# HB-UNI-Sen-TEMP-DS18B20_V1_0.net
KiCad netlist of a schematic drawn in EAGLE
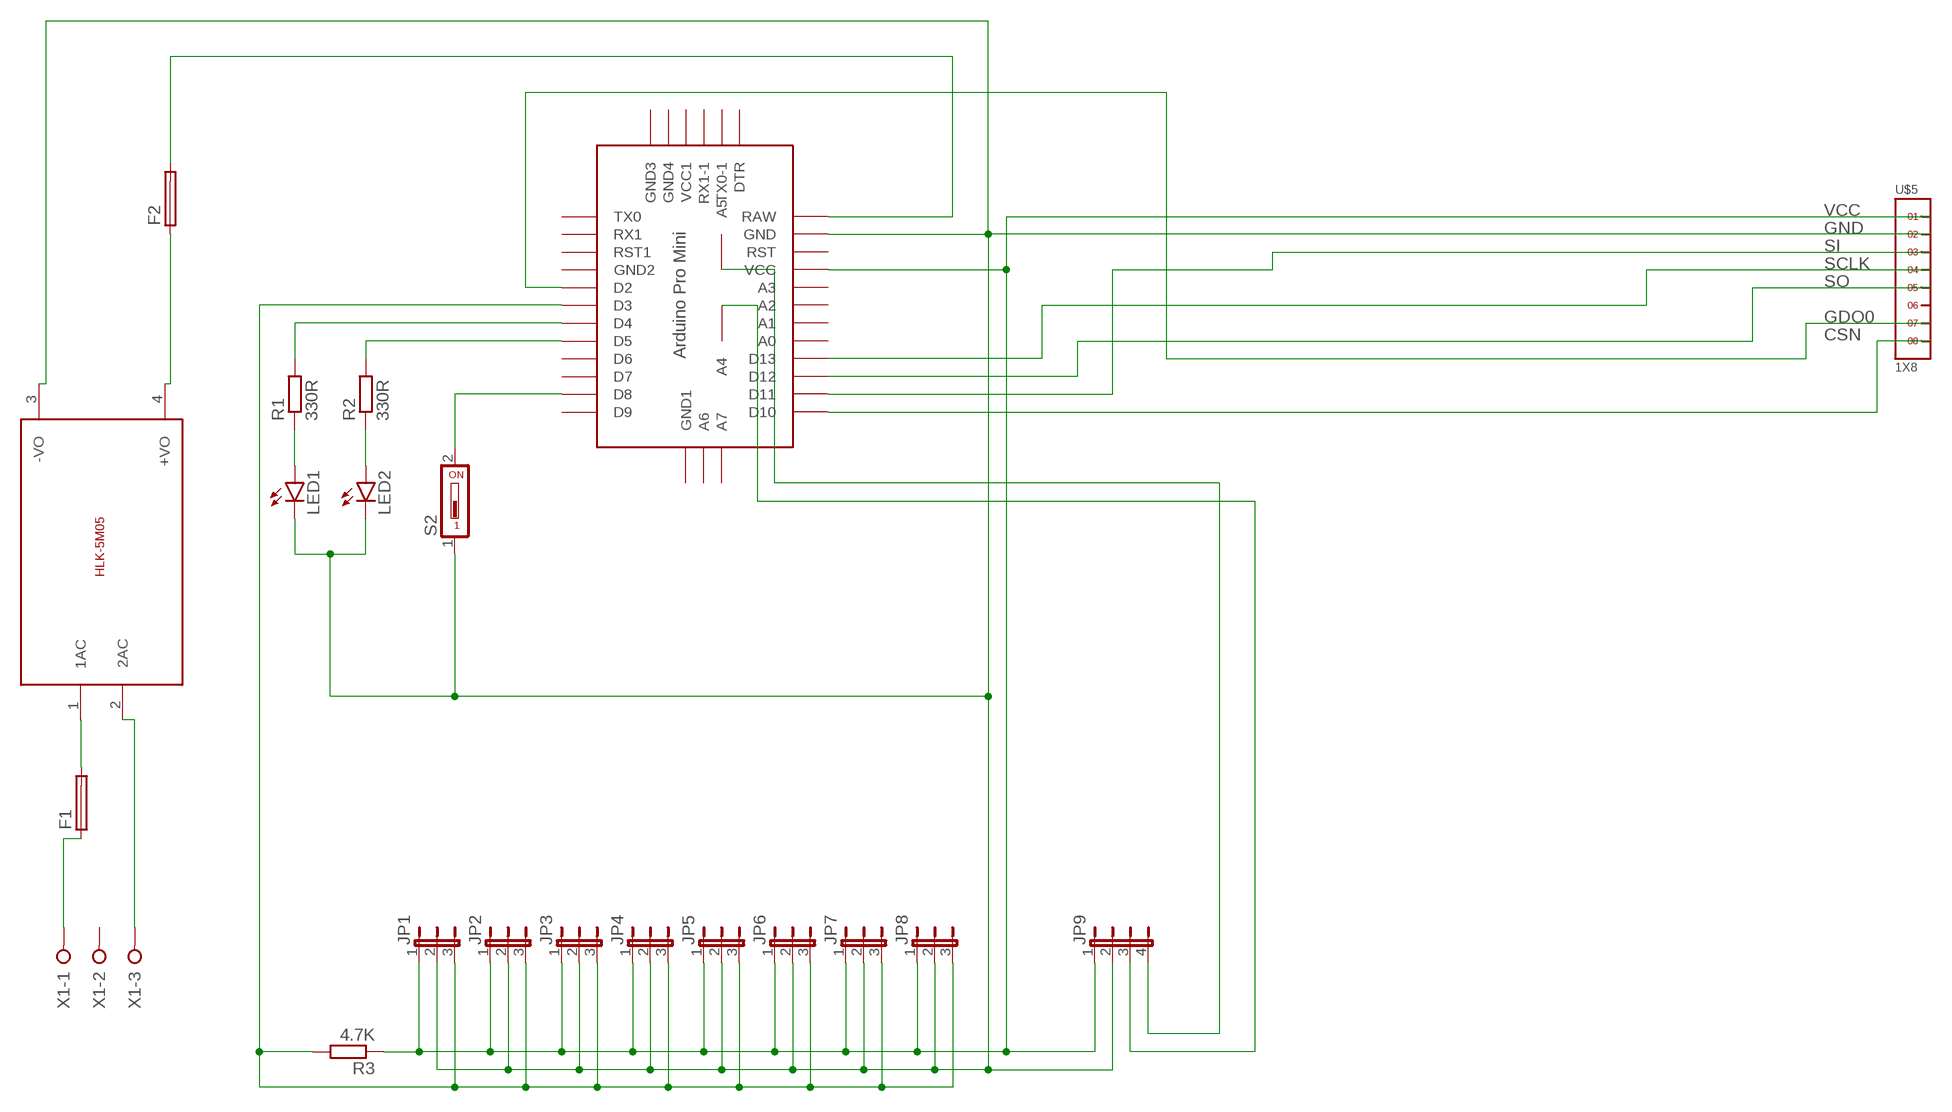
[diagram p0: schematic, sheet 1]

(export (version "E")
  (design (tool "Eeschema 10.0.6"))
  (components
    (comp (ref "F1")
      (value "GSH15")
      (footprint "eagle-import:GSH15")
      (fields (field (name "MPN") "64900001039"))
      (libsource (lib "eagle-import") (part "GSH15"))
    )
    (comp (ref "F2")
      (value "GSH15")
      (footprint "eagle-import:GSH15")
      (fields (field (name "MPN") "64900001039"))
      (libsource (lib "eagle-import") (part "GSH15"))
    )
    (comp (ref "JP1")
      (value "JP2W")
      (footprint "eagle-import:JP2W")
      (libsource (lib "eagle-import") (part "JP2W"))
    )
    (comp (ref "JP2")
      (value "JP2W")
      (footprint "eagle-import:JP2W")
      (libsource (lib "eagle-import") (part "JP2W"))
    )
    (comp (ref "JP3")
      (value "JP2W")
      (footprint "eagle-import:JP2W")
      (libsource (lib "eagle-import") (part "JP2W"))
    )
    (comp (ref "JP4")
      (value "JP2W")
      (footprint "eagle-import:JP2W")
      (libsource (lib "eagle-import") (part "JP2W"))
    )
    (comp (ref "JP5")
      (value "JP2W")
      (footprint "eagle-import:JP2W")
      (libsource (lib "eagle-import") (part "JP2W"))
    )
    (comp (ref "JP6")
      (value "JP2W")
      (footprint "eagle-import:JP2W")
      (libsource (lib "eagle-import") (part "JP2W"))
    )
    (comp (ref "JP7")
      (value "JP2W")
      (footprint "eagle-import:JP2W")
      (libsource (lib "eagle-import") (part "JP2W"))
    )
    (comp (ref "JP8")
      (value "JP2W")
      (footprint "eagle-import:JP2W")
      (libsource (lib "eagle-import") (part "JP2W"))
    )
    (comp (ref "JP9")
      (value "JP4E")
      (footprint "eagle-import:JP4")
      (libsource (lib "eagle-import") (part "JP4E"))
    )
    (comp (ref "LED1")
      (value "LED5MM")
      (footprint "eagle-import:LED5MM")
      (libsource (lib "eagle-import") (part "LED5MM"))
    )
    (comp (ref "LED2")
      (value "LED5MM")
      (footprint "eagle-import:LED5MM")
      (libsource (lib "eagle-import") (part "LED5MM"))
    )
    (comp (ref "R1")
      (value "330R")
      (footprint "eagle-import:0207_10")
      (libsource (lib "eagle-import") (part "R-EU_0207/10"))
    )
    (comp (ref "R2")
      (value "330R")
      (footprint "eagle-import:0207_10")
      (libsource (lib "eagle-import") (part "R-EU_0207/10"))
    )
    (comp (ref "R3")
      (value "4.7K")
      (footprint "eagle-import:0207_10")
      (libsource (lib "eagle-import") (part "R-EU_0207/10"))
    )
    (comp (ref "S2")
      (value "DS01")
      (footprint "eagle-import:DS-01")
      (libsource (lib "eagle-import") (part "DS01"))
    )
    (comp (ref "U$1")
      (value "ABK-PRO-MINI")
      (footprint "eagle-import:ABK-PRO-MINI")
      (libsource (lib "eagle-import") (part "ABK-PRO-MINI"))
    )
    (comp (ref "U$3")
      (value "5VDC/5W")
      (footprint "eagle-import:HLK-5M05")
      (libsource (lib "eagle-import") (part "HLK-5M05"))
    )
    (comp (ref "U$5")
      (value "1X8")
      (footprint "eagle-import:1X8")
      (libsource (lib "eagle-import") (part "1X8"))
    )
    (comp (ref "X1")
      (value "W237-3E")
      (footprint "eagle-import:W237-3E")
      (libsource (lib "eagle-import") (part "W237-3E"))
    )
  )
  (nets
    (net (code "1") (name "/CSN") (class "Default")
      (node (ref "U$1") (pin "D10") (pinfunction "D10_D10") (pintype "bidirectional"))
      (node (ref "U$5") (pin "8") (pinfunction "8_8") (pintype "bidirectional"))
    )
    (net (code "2") (name "/GDO0") (class "Default")
      (node (ref "U$1") (pin "D2") (pinfunction "D2_D2") (pintype "bidirectional"))
      (node (ref "U$5") (pin "7") (pinfunction "7_7") (pintype "bidirectional"))
    )
    (net (code "3") (name "/GND") (class "Default")
      (node (ref "JP1") (pin "2") (pinfunction "2_2") (pintype "passive"))
      (node (ref "JP2") (pin "2") (pinfunction "2_2") (pintype "passive"))
      (node (ref "JP3") (pin "2") (pinfunction "2_2") (pintype "passive"))
      (node (ref "JP4") (pin "2") (pinfunction "2_2") (pintype "passive"))
      (node (ref "JP5") (pin "2") (pinfunction "2_2") (pintype "passive"))
      (node (ref "JP6") (pin "2") (pinfunction "2_2") (pintype "passive"))
      (node (ref "JP7") (pin "2") (pinfunction "2_2") (pintype "passive"))
      (node (ref "JP8") (pin "2") (pinfunction "2_2") (pintype "passive"))
      (node (ref "JP9") (pin "2") (pinfunction "2_2") (pintype "passive"))
      (node (ref "LED1") (pin "K") (pinfunction "C_K") (pintype "passive"))
      (node (ref "LED2") (pin "K") (pinfunction "C_K") (pintype "passive"))
      (node (ref "S2") (pin "1") (pinfunction "1_1") (pintype "passive"))
      (node (ref "U$1") (pin "GND") (pinfunction "GND_GND") (pintype "bidirectional"))
      (node (ref "U$3") (pin "3") (pinfunction "-VO_3") (pintype "bidirectional"))
      (node (ref "U$5") (pin "2") (pinfunction "2_2") (pintype "bidirectional"))
    )
    (net (code "4") (name "/SCLK") (class "Default")
      (node (ref "U$1") (pin "D13") (pinfunction "D13_D13") (pintype "bidirectional"))
      (node (ref "U$5") (pin "4") (pinfunction "4_4") (pintype "bidirectional"))
    )
    (net (code "5") (name "/SI") (class "Default")
      (node (ref "U$1") (pin "D11") (pinfunction "D11_D11") (pintype "bidirectional"))
      (node (ref "U$5") (pin "3") (pinfunction "3_3") (pintype "bidirectional"))
    )
    (net (code "6") (name "/SO") (class "Default")
      (node (ref "U$1") (pin "D12") (pinfunction "D12_D12") (pintype "bidirectional"))
      (node (ref "U$5") (pin "5") (pinfunction "5_5") (pintype "bidirectional"))
    )
    (net (code "7") (name "/VCC") (class "Default")
      (node (ref "JP1") (pin "1") (pinfunction "1_1") (pintype "passive"))
      (node (ref "JP2") (pin "1") (pinfunction "1_1") (pintype "passive"))
      (node (ref "JP3") (pin "1") (pinfunction "1_1") (pintype "passive"))
      (node (ref "JP4") (pin "1") (pinfunction "1_1") (pintype "passive"))
      (node (ref "JP5") (pin "1") (pinfunction "1_1") (pintype "passive"))
      (node (ref "JP6") (pin "1") (pinfunction "1_1") (pintype "passive"))
      (node (ref "JP7") (pin "1") (pinfunction "1_1") (pintype "passive"))
      (node (ref "JP8") (pin "1") (pinfunction "1_1") (pintype "passive"))
      (node (ref "JP9") (pin "1") (pinfunction "1_1") (pintype "passive"))
      (node (ref "R3") (pin "1") (pinfunction "1_1") (pintype "passive"))
      (node (ref "U$1") (pin "VCC") (pinfunction "VCC_VCC") (pintype "bidirectional"))
      (node (ref "U$5") (pin "1") (pinfunction "1_1") (pintype "bidirectional"))
    )
    (net (code "8") (name "Net-(F2-Pad2)") (class "Default")
      (node (ref "F2") (pin "2") (pinfunction "2_2") (pintype "passive"))
      (node (ref "U$1") (pin "RAW") (pinfunction "RAW_RAW") (pintype "bidirectional"))
    )
    (net (code "9") (name "Net-(JP1-Pad3)") (class "Default")
      (node (ref "JP1") (pin "3") (pinfunction "3_3") (pintype "passive"))
      (node (ref "JP2") (pin "3") (pinfunction "3_3") (pintype "passive"))
      (node (ref "JP3") (pin "3") (pinfunction "3_3") (pintype "passive"))
      (node (ref "JP4") (pin "3") (pinfunction "3_3") (pintype "passive"))
      (node (ref "JP5") (pin "3") (pinfunction "3_3") (pintype "passive"))
      (node (ref "JP6") (pin "3") (pinfunction "3_3") (pintype "passive"))
      (node (ref "JP7") (pin "3") (pinfunction "3_3") (pintype "passive"))
      (node (ref "JP8") (pin "3") (pinfunction "3_3") (pintype "passive"))
      (node (ref "R3") (pin "2") (pinfunction "2_2") (pintype "passive"))
      (node (ref "U$1") (pin "D3") (pinfunction "D3_D3") (pintype "bidirectional"))
    )
    (net (code "10") (name "Net-(JP9-Pad3)") (class "Default")
      (node (ref "JP9") (pin "3") (pinfunction "3_3") (pintype "passive"))
      (node (ref "U$1") (pin "A4") (pinfunction "A4_A4") (pintype "bidirectional"))
    )
    (net (code "11") (name "Net-(JP9-Pad4)") (class "Default")
      (node (ref "JP9") (pin "4") (pinfunction "4_4") (pintype "passive"))
      (node (ref "U$1") (pin "A5") (pinfunction "A5_A5") (pintype "bidirectional"))
    )
    (net (code "12") (name "Net-(LED1-PadA)") (class "Default")
      (node (ref "LED1") (pin "A") (pinfunction "A_A") (pintype "passive"))
      (node (ref "R1") (pin "1") (pinfunction "1_1") (pintype "passive"))
    )
    (net (code "13") (name "Net-(LED2-PadA)") (class "Default")
      (node (ref "LED2") (pin "A") (pinfunction "A_A") (pintype "passive"))
      (node (ref "R2") (pin "1") (pinfunction "1_1") (pintype "passive"))
    )
    (net (code "14") (name "Net-(R1-Pad2)") (class "Default")
      (node (ref "R1") (pin "2") (pinfunction "2_2") (pintype "passive"))
      (node (ref "U$1") (pin "D4") (pinfunction "D4_D4") (pintype "bidirectional"))
    )
    (net (code "15") (name "Net-(R2-Pad2)") (class "Default")
      (node (ref "R2") (pin "2") (pinfunction "2_2") (pintype "passive"))
      (node (ref "U$1") (pin "D5") (pinfunction "D5_D5") (pintype "bidirectional"))
    )
    (net (code "16") (name "Net-(S2-Pad2)") (class "Default")
      (node (ref "S2") (pin "2") (pinfunction "2_2") (pintype "passive"))
      (node (ref "U$1") (pin "D8") (pinfunction "D8_D8") (pintype "bidirectional"))
    )
    (net (code "17") (name "Net-(U$3-+VO)") (class "Default")
      (node (ref "F2") (pin "1") (pinfunction "1_1") (pintype "passive"))
      (node (ref "U$3") (pin "4") (pinfunction "+VO_4") (pintype "bidirectional"))
    )
    (net (code "18") (name "Net-(U$3-1AC)") (class "Default")
      (node (ref "F1") (pin "2") (pinfunction "2_2") (pintype "passive"))
      (node (ref "U$3") (pin "1") (pinfunction "1AC_1") (pintype "bidirectional"))
    )
    (net (code "19") (name "Net-(U$3-2AC)") (class "Default")
      (node (ref "U$3") (pin "2") (pinfunction "2AC_2") (pintype "bidirectional"))
      (node (ref "X1") (pin "3") (pinfunction "KL_3") (pintype "passive"))
    )
    (net (code "20") (name "Net-(X1A-KL)") (class "Default")
      (node (ref "F1") (pin "1") (pinfunction "1_1") (pintype "passive"))
      (node (ref "X1") (pin "1") (pinfunction "KL_1") (pintype "passive"))
    )
    (net (code "21") (name "unconnected-(U$1-GND1-PadGND4)") (class "Default")
      (node (ref "U$1") (pin "GND4") (pinfunction "GND1_GND4") (pintype "bidirectional"))
    )
    (net (code "22") (name "unconnected-(U$1-GND2-PadGND1)") (class "Default")
      (node (ref "U$1") (pin "GND1") (pinfunction "GND2_GND1") (pintype "bidirectional"))
    )
    (net (code "23") (name "unconnected-(U$1-GND3-PadGND2)") (class "Default")
      (node (ref "U$1") (pin "GND2") (pinfunction "GND3_GND2") (pintype "bidirectional"))
    )
    (net (code "24") (name "unconnected-(U$1-GND4-PadGND3)") (class "Default")
      (node (ref "U$1") (pin "GND3") (pinfunction "GND4_GND3") (pintype "bidirectional"))
    )
    (net (code "25") (name "unconnected-(U$1-PadA0)") (class "Default")
      (node (ref "U$1") (pin "A0") (pinfunction "A0_A0") (pintype "bidirectional"))
    )
    (net (code "26") (name "unconnected-(U$1-PadA1)") (class "Default")
      (node (ref "U$1") (pin "A1") (pinfunction "A1_A1") (pintype "bidirectional"))
    )
    (net (code "27") (name "unconnected-(U$1-PadA2)") (class "Default")
      (node (ref "U$1") (pin "A2") (pinfunction "A2_A2") (pintype "bidirectional"))
    )
    (net (code "28") (name "unconnected-(U$1-PadA3)") (class "Default")
      (node (ref "U$1") (pin "A3") (pinfunction "A3_A3") (pintype "bidirectional"))
    )
    (net (code "29") (name "unconnected-(U$1-PadA6)") (class "Default")
      (node (ref "U$1") (pin "A6") (pinfunction "A6_A6") (pintype "bidirectional"))
    )
    (net (code "30") (name "unconnected-(U$1-PadA7)") (class "Default")
      (node (ref "U$1") (pin "A7") (pinfunction "A7_A7") (pintype "bidirectional"))
    )
    (net (code "31") (name "unconnected-(U$1-PadD6)") (class "Default")
      (node (ref "U$1") (pin "D6") (pinfunction "D6_D6") (pintype "bidirectional"))
    )
    (net (code "32") (name "unconnected-(U$1-PadD7)") (class "Default")
      (node (ref "U$1") (pin "D7") (pinfunction "D7_D7") (pintype "bidirectional"))
    )
    (net (code "33") (name "unconnected-(U$1-PadD9)") (class "Default")
      (node (ref "U$1") (pin "D9") (pinfunction "D9_D9") (pintype "bidirectional"))
    )
    (net (code "34") (name "unconnected-(U$1-PadDTR)") (class "Default")
      (node (ref "U$1") (pin "DTR") (pinfunction "DTR_DTR") (pintype "bidirectional"))
    )
    (net (code "35") (name "unconnected-(U$1-PadRST)") (class "Default")
      (node (ref "U$1") (pin "RST") (pinfunction "RST_RST") (pintype "bidirectional"))
    )
    (net (code "36") (name "unconnected-(U$1-PadRST1)") (class "Default")
      (node (ref "U$1") (pin "RST1") (pinfunction "RST1_RST1") (pintype "bidirectional"))
    )
    (net (code "37") (name "unconnected-(U$1-PadRX1)") (class "Default")
      (node (ref "U$1") (pin "RX1") (pinfunction "RX1_RX1") (pintype "bidirectional"))
    )
    (net (code "38") (name "unconnected-(U$1-PadRX1-1)") (class "Default")
      (node (ref "U$1") (pin "RX1-1") (pinfunction "RX1-1_RX1-1") (pintype "bidirectional"))
    )
    (net (code "39") (name "unconnected-(U$1-PadTX0)") (class "Default")
      (node (ref "U$1") (pin "TX0") (pinfunction "TX0_TX0") (pintype "bidirectional"))
    )
    (net (code "40") (name "unconnected-(U$1-PadTX0-1)") (class "Default")
      (node (ref "U$1") (pin "TX0-1") (pinfunction "TX0-1_TX0-1") (pintype "bidirectional"))
    )
    (net (code "41") (name "unconnected-(U$1-PadVCC1)") (class "Default")
      (node (ref "U$1") (pin "VCC1") (pinfunction "VCC1_VCC1") (pintype "bidirectional"))
    )
    (net (code "42") (name "unconnected-(U$5-Pad6)") (class "Default")
      (node (ref "U$5") (pin "6") (pinfunction "6_6") (pintype "bidirectional"))
    )
    (net (code "43") (name "unconnected-(X1B-KL-Pad2)") (class "Default")
      (node (ref "X1") (pin "2") (pinfunction "KL_2") (pintype "passive"))
    )
  )
)
